# power_POS3V3.net
KiCad netlist of a schematic drawn in Altium Designer
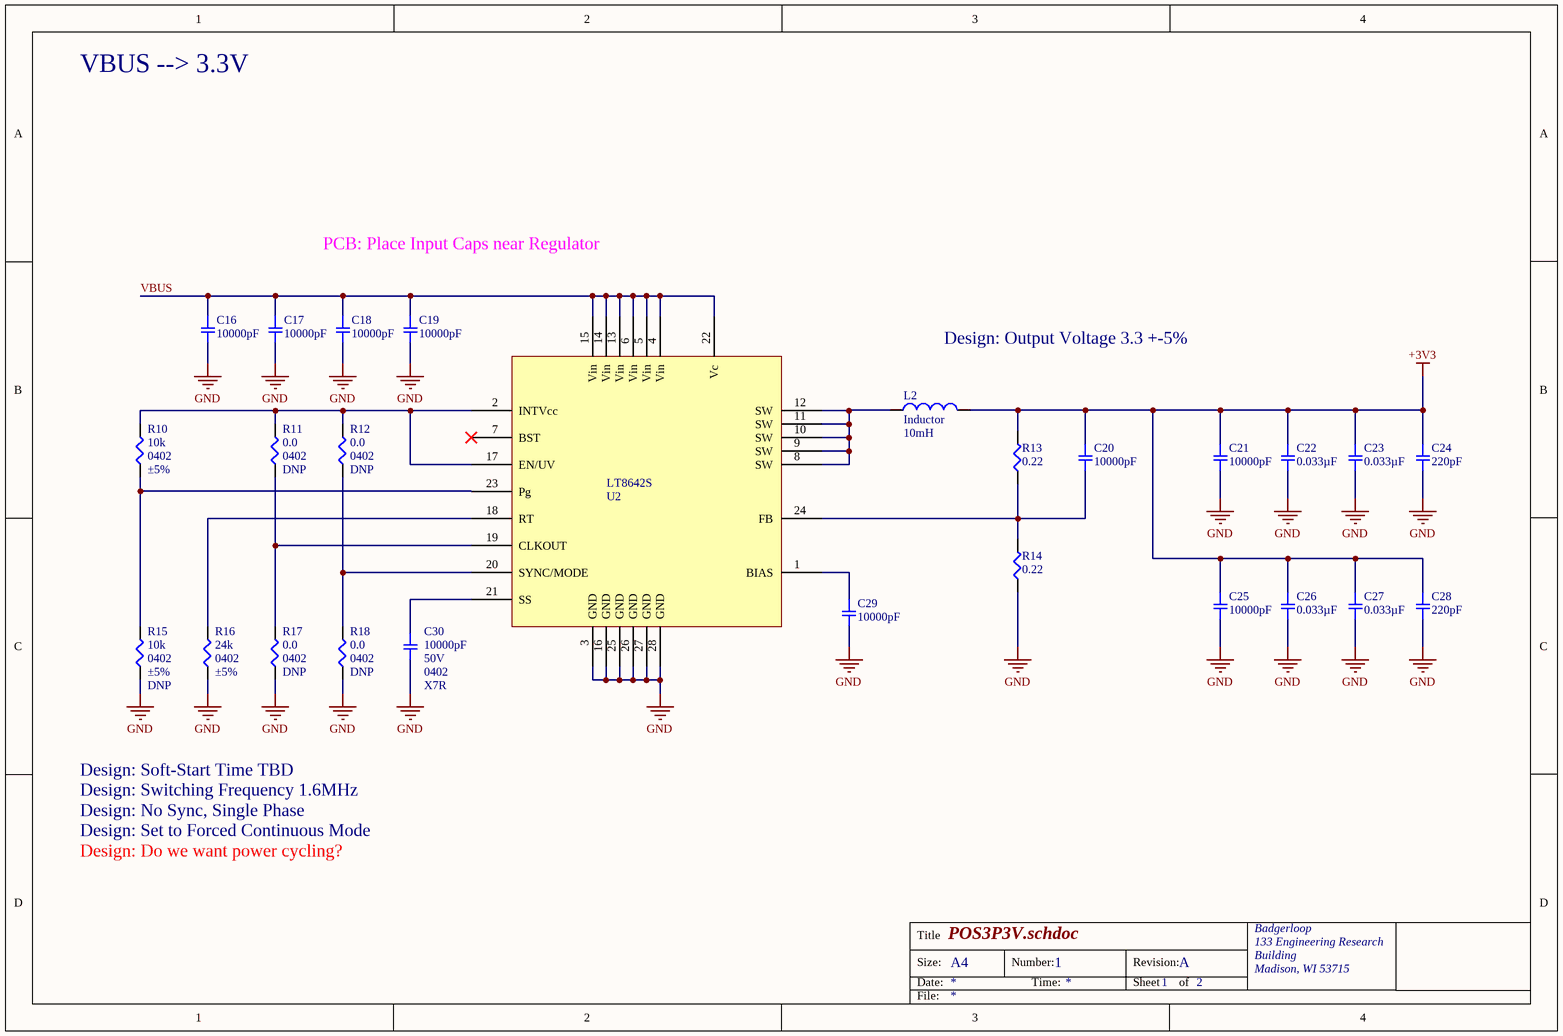
[diagram p0: power_POS3V3.schdoc]

(export (version "E")
  (design (tool "Eeschema 10.0.6"))
  (components
    (comp (ref "C16")
      (value "10000pF")
      (footprint "SMD-0805C")
      (description "CAP CER 10000PF 250V X7T 0805")
      (fields
        (field (name "DIGI-KEY PART NUMBER") "490-13986-1-ND")
        (field (name "PART NUMBER") "GC321AD72E103KX01D")
      )
      (libsource (lib "capacitor") (part "GC321AD72E103KX01D"))
    )
    (comp (ref "C17")
      (value "10000pF")
      (footprint "SMD-0805C")
      (description "CAP CER 10000PF 250V X7T 0805")
      (fields
        (field (name "DIGI-KEY PART NUMBER") "490-13986-1-ND")
        (field (name "PART NUMBER") "GC321AD72E103KX01D")
      )
      (libsource (lib "capacitor") (part "GC321AD72E103KX01D"))
    )
    (comp (ref "C18")
      (value "10000pF")
      (footprint "SMD-0805C")
      (description "CAP CER 10000PF 250V X7T 0805")
      (fields
        (field (name "DIGI-KEY PART NUMBER") "490-13986-1-ND")
        (field (name "PART NUMBER") "GC321AD72E103KX01D")
      )
      (libsource (lib "capacitor") (part "GC321AD72E103KX01D"))
    )
    (comp (ref "C19")
      (value "10000pF")
      (footprint "SMD-0805C")
      (description "CAP CER 10000PF 250V X7T 0805")
      (fields
        (field (name "DIGI-KEY PART NUMBER") "490-13986-1-ND")
        (field (name "PART NUMBER") "GC321AD72E103KX01D")
      )
      (libsource (lib "capacitor") (part "GC321AD72E103KX01D"))
    )
    (comp (ref "C20")
      (value "10000pF")
      (footprint "SMD-0805C")
      (description "CAP CER 10000PF 250V X7T 0805")
      (fields
        (field (name "DIGI-KEY PART NUMBER") "490-13986-1-ND")
        (field (name "PART NUMBER") "GC321AD72E103KX01D")
      )
      (libsource (lib "capacitor") (part "GC321AD72E103KX01D"))
    )
    (comp (ref "C21")
      (value "10000pF")
      (footprint "SMD-0805C")
      (description "CAP CER 10000PF 250V X7T 0805")
      (fields
        (field (name "DIGI-KEY PART NUMBER") "490-13986-1-ND")
        (field (name "PART NUMBER") "GC321AD72E103KX01D")
      )
      (libsource (lib "capacitor") (part "GC321AD72E103KX01D"))
    )
    (comp (ref "C22")
      (value "0.033µF")
      (footprint "SMD-1206C")
      (description "CAP CER 0.033UF 250V X7T 1206")
      (fields
        (field (name "DIGI-KEY PART NUMBER") "490-13989-1-ND")
        (field (name "PART NUMBER") "GC331AD72E333KX01D")
      )
      (libsource (lib "capacitor") (part "GC331AD72E333KX01D"))
    )
    (comp (ref "C23")
      (value "0.033µF")
      (footprint "SMD-1206C")
      (description "CAP CER 0.033UF 250V X7T 1206")
      (fields
        (field (name "DIGI-KEY PART NUMBER") "490-13989-1-ND")
        (field (name "PART NUMBER") "GC331AD72E333KX01D")
      )
      (libsource (lib "capacitor") (part "GC331AD72E333KX01D"))
    )
    (comp (ref "C24")
      (value "220pF")
      (footprint "SMD-0402C")
      (description "CAP CER 220PF 50V NP0 0402")
      (fields
        (field (name "DIGI-KEY PART NUMBER") "490-4927-1-ND")
        (field (name "PART NUMBER") "GCM1555C1H221JA16D")
      )
      (libsource (lib "capacitor") (part "GCM1555C1H221JA16D"))
    )
    (comp (ref "C25")
      (value "10000pF")
      (footprint "SMD-0805C")
      (description "CAP CER 10000PF 250V X7T 0805")
      (fields
        (field (name "DIGI-KEY PART NUMBER") "490-13986-1-ND")
        (field (name "PART NUMBER") "GC321AD72E103KX01D")
      )
      (libsource (lib "capacitor") (part "GC321AD72E103KX01D"))
    )
    (comp (ref "C26")
      (value "0.033µF")
      (footprint "SMD-1206C")
      (description "CAP CER 0.033UF 250V X7T 1206")
      (fields
        (field (name "DIGI-KEY PART NUMBER") "490-13989-1-ND")
        (field (name "PART NUMBER") "GC331AD72E333KX01D")
      )
      (libsource (lib "capacitor") (part "GC331AD72E333KX01D"))
    )
    (comp (ref "C27")
      (value "0.033µF")
      (footprint "SMD-1206C")
      (description "CAP CER 0.033UF 250V X7T 1206")
      (fields
        (field (name "DIGI-KEY PART NUMBER") "490-13989-1-ND")
        (field (name "PART NUMBER") "GC331AD72E333KX01D")
      )
      (libsource (lib "capacitor") (part "GC331AD72E333KX01D"))
    )
    (comp (ref "C28")
      (value "220pF")
      (footprint "SMD-0402C")
      (description "CAP CER 220PF 50V NP0 0402")
      (fields
        (field (name "DIGI-KEY PART NUMBER") "490-4927-1-ND")
        (field (name "PART NUMBER") "GCM1555C1H221JA16D")
      )
      (libsource (lib "capacitor") (part "GCM1555C1H221JA16D"))
    )
    (comp (ref "C29")
      (value "10000pF")
      (footprint "SMD-0805C")
      (description "CAP CER 10000PF 250V X7T 0805")
      (fields
        (field (name "DIGI-KEY PART NUMBER") "490-13986-1-ND")
        (field (name "PART NUMBER") "GC321AD72E103KX01D")
      )
      (libsource (lib "capacitor") (part "GC321AD72E103KX01D"))
    )
    (comp (ref "C30")
      (value "10000pF")
      (footprint "SMD-0402C")
      (description "CAP CER 10000PF 50V X7R 0402")
      (fields
        (field (name "DIGI-KEY PART NUMBER") "490-4762-1-ND")
        (field (name "PART NUMBER") "GCM155R71H103KA55D")
        (field (name "VOLTAGE") "50V")
        (field (name "TEMPERATURE COEFFICIENT") "X7R")
        (field (name "PACKAGE / CASE") "0402")
      )
      (libsource (lib "capacitor") (part "GCM155R71H103KA55D"))
    )
    (comp (ref "L2")
      (value "Inductor")
      (footprint "0402-A")
      (fields (field (name "ALTIUM_VALUE") "10mH") (field (name "PUBLISHER") "Altium Limited"))
      (libsource (lib "Miscellaneous Devices") (part "Inductor"))
    )
    (comp (ref "R10")
      (value "10k")
      (footprint "SMD-0402-RES")
      (description "RES SMD 10K OHM 5% 1/10W 0402")
      (fields
        (field (name "PART NUMBER") "ERJ-2GEJ103X")
        (field (name "DIGI-KEY PART NUMBER") "P10KJCT-ND")
        (field (name "TOLERANCE") "±5%")
        (field (name "SUPPLIER DEVICE PACKAGE") "0402")
      )
      (libsource (lib "resistor") (part "ERJ-2GEJ103X"))
    )
    (comp (ref "R11")
      (value "0.0")
      (footprint "SMD-0402-RES")
      (description "RES SMD 0.0OHM JUMPER 1/10W 0402")
      (fields
        (field (name "PART NUMBER") "ERJ-2GE0R00X")
        (field (name "DIGI-KEY PART NUMBER") "P0.0JCT-ND")
        (field (name "SUPPLIER DEVICE PACKAGE") "0402")
        (field (name "BOM") "DNP")
      )
      (libsource (lib "resistor") (part "ERJ-2GE0R00X"))
    )
    (comp (ref "R12")
      (value "0.0")
      (footprint "SMD-0402-RES")
      (description "RES SMD 0.0OHM JUMPER 1/10W 0402")
      (fields
        (field (name "PART NUMBER") "ERJ-2GE0R00X")
        (field (name "DIGI-KEY PART NUMBER") "P0.0JCT-ND")
        (field (name "SUPPLIER DEVICE PACKAGE") "0402")
        (field (name "BOM") "DNP")
      )
      (libsource (lib "resistor") (part "ERJ-2GE0R00X"))
    )
    (comp (ref "R13")
      (value "0.22")
      (footprint "SMD-0402-RES")
      (description "RES SMD 0.22 OHM 1% 1/6W 0402")
      (fields (field (name "PART NUMBER") "ERJ-2BQFR22X") (field (name "DIGI-KEY PART NUMBER") "P.22AKCT-ND"))
      (libsource (lib "resistor") (part "ERJ-2BQFR22X"))
    )
    (comp (ref "R14")
      (value "0.22")
      (footprint "SMD-0402-RES")
      (description "RES SMD 0.22 OHM 1% 1/6W 0402")
      (fields (field (name "PART NUMBER") "ERJ-2BQFR22X") (field (name "DIGI-KEY PART NUMBER") "P.22AKCT-ND"))
      (libsource (lib "resistor") (part "ERJ-2BQFR22X"))
    )
    (comp (ref "R15")
      (value "10k")
      (footprint "SMD-0402-RES")
      (description "RES SMD 10K OHM 5% 1/10W 0402")
      (fields
        (field (name "PART NUMBER") "ERJ-2GEJ103X")
        (field (name "DIGI-KEY PART NUMBER") "P10KJCT-ND")
        (field (name "TOLERANCE") "±5%")
        (field (name "SUPPLIER DEVICE PACKAGE") "0402")
        (field (name "BOM_CONFIG") "DNP")
      )
      (libsource (lib "resistor") (part "ERJ-2GEJ103X"))
    )
    (comp (ref "R16")
      (value "24k")
      (footprint "SMD-0402-RES")
      (description "RES SMD 24K OHM 5% 1/10W 0402")
      (fields
        (field (name "PART NUMBER") "ERJ-2GEJ243X")
        (field (name "DIGI-KEY PART NUMBER") "P24KJCT-ND")
        (field (name "TOLERANCE") "±5%")
        (field (name "SUPPLIER DEVICE PACKAGE") "0402")
      )
      (libsource (lib "resistor") (part "ERJ-2GEJ243X"))
    )
    (comp (ref "R17")
      (value "0.0")
      (footprint "SMD-0402-RES")
      (description "RES SMD 0.0OHM JUMPER 1/10W 0402")
      (fields
        (field (name "PART NUMBER") "ERJ-2GE0R00X")
        (field (name "DIGI-KEY PART NUMBER") "P0.0JCT-ND")
        (field (name "SUPPLIER DEVICE PACKAGE") "0402")
        (field (name "BOM") "DNP")
      )
      (libsource (lib "resistor") (part "ERJ-2GE0R00X"))
    )
    (comp (ref "R18")
      (value "0.0")
      (footprint "SMD-0402-RES")
      (description "RES SMD 0.0OHM JUMPER 1/10W 0402")
      (fields
        (field (name "PART NUMBER") "ERJ-2GE0R00X")
        (field (name "DIGI-KEY PART NUMBER") "P0.0JCT-ND")
        (field (name "SUPPLIER DEVICE PACKAGE") "0402")
        (field (name "BOM") "DNP")
      )
      (libsource (lib "resistor") (part "ERJ-2GE0R00X"))
    )
    (comp (ref "U2")
      (value "LT8642S")
      (description "18V, 10A Synchronous\r\nStep-Down Silent Switcher 2")
      (libsource (lib "ic") (part "LT8642S"))
    )
  )
  (nets
    (net (code "1") (name "+3V3") (class "Default")
      (node (ref "C20") (pin "1") (pinfunction "1_1") (pintype "passive"))
      (node (ref "C21") (pin "1") (pinfunction "1_1") (pintype "passive"))
      (node (ref "C22") (pin "1") (pinfunction "1_1") (pintype "passive"))
      (node (ref "C23") (pin "1") (pinfunction "1_1") (pintype "passive"))
      (node (ref "C24") (pin "1") (pinfunction "1_1") (pintype "passive"))
      (node (ref "C25") (pin "1") (pinfunction "1_1") (pintype "passive"))
      (node (ref "C26") (pin "1") (pinfunction "1_1") (pintype "passive"))
      (node (ref "C27") (pin "1") (pinfunction "1_1") (pintype "passive"))
      (node (ref "C28") (pin "1") (pinfunction "1_1") (pintype "passive"))
      (node (ref "L2") (pin "2") (pinfunction "2_2") (pintype "passive"))
      (node (ref "R13") (pin "2") (pinfunction "2_2") (pintype "passive"))
    )
    (net (code "2") (name "/VBUS") (class "Default")
      (node (ref "C16") (pin "1") (pinfunction "1_1") (pintype "passive"))
      (node (ref "C17") (pin "1") (pinfunction "1_1") (pintype "passive"))
      (node (ref "C18") (pin "1") (pinfunction "1_1") (pintype "passive"))
      (node (ref "C19") (pin "1") (pinfunction "1_1") (pintype "passive"))
      (node (ref "U2") (pin "13") (pinfunction "Vin_13") (pintype "power_in"))
      (node (ref "U2") (pin "14") (pinfunction "Vin_14") (pintype "power_in"))
      (node (ref "U2") (pin "15") (pinfunction "Vin_15") (pintype "power_in"))
      (node (ref "U2") (pin "22") (pinfunction "Vc_22") (pintype "passive"))
      (node (ref "U2") (pin "4") (pinfunction "Vin_4") (pintype "power_in"))
      (node (ref "U2") (pin "5") (pinfunction "Vin_5") (pintype "power_in"))
      (node (ref "U2") (pin "6") (pinfunction "Vin_6") (pintype "power_in"))
    )
    (net (code "3") (name "GND") (class "Default")
      (node (ref "C16") (pin "2") (pinfunction "2_2") (pintype "passive"))
      (node (ref "C17") (pin "2") (pinfunction "2_2") (pintype "passive"))
      (node (ref "C18") (pin "2") (pinfunction "2_2") (pintype "passive"))
      (node (ref "C19") (pin "2") (pinfunction "2_2") (pintype "passive"))
      (node (ref "C21") (pin "2") (pinfunction "2_2") (pintype "passive"))
      (node (ref "C22") (pin "2") (pinfunction "2_2") (pintype "passive"))
      (node (ref "C23") (pin "2") (pinfunction "2_2") (pintype "passive"))
      (node (ref "C24") (pin "2") (pinfunction "2_2") (pintype "passive"))
      (node (ref "C25") (pin "2") (pinfunction "2_2") (pintype "passive"))
      (node (ref "C26") (pin "2") (pinfunction "2_2") (pintype "passive"))
      (node (ref "C27") (pin "2") (pinfunction "2_2") (pintype "passive"))
      (node (ref "C28") (pin "2") (pinfunction "2_2") (pintype "passive"))
      (node (ref "C29") (pin "2") (pinfunction "2_2") (pintype "passive"))
      (node (ref "C30") (pin "2") (pinfunction "2_2") (pintype "passive"))
      (node (ref "R14") (pin "1") (pinfunction "1_1") (pintype "passive"))
      (node (ref "R15") (pin "1") (pinfunction "1_1") (pintype "passive"))
      (node (ref "R16") (pin "1") (pinfunction "1_1") (pintype "passive"))
      (node (ref "R17") (pin "1") (pinfunction "1_1") (pintype "passive"))
      (node (ref "R18") (pin "1") (pinfunction "1_1") (pintype "passive"))
      (node (ref "U2") (pin "16") (pinfunction "GND_16") (pintype "power_in"))
      (node (ref "U2") (pin "25") (pinfunction "GND_25") (pintype "power_in"))
      (node (ref "U2") (pin "26") (pinfunction "GND_26") (pintype "power_in"))
      (node (ref "U2") (pin "27") (pinfunction "GND_27") (pintype "power_in"))
      (node (ref "U2") (pin "28") (pinfunction "GND_28") (pintype "power_in"))
      (node (ref "U2") (pin "3") (pinfunction "GND_3") (pintype "power_in"))
    )
    (net (code "4") (name "Net-(L2-Pad1)") (class "Default")
      (node (ref "L2") (pin "1") (pinfunction "1_1") (pintype "passive"))
      (node (ref "U2") (pin "10") (pinfunction "SW_10") (pintype "passive"))
      (node (ref "U2") (pin "11") (pinfunction "SW_11") (pintype "passive"))
      (node (ref "U2") (pin "12") (pinfunction "SW_12") (pintype "passive"))
      (node (ref "U2") (pin "8") (pinfunction "SW_8") (pintype "passive"))
      (node (ref "U2") (pin "9") (pinfunction "SW_9") (pintype "passive"))
    )
    (net (code "5") (name "Net-(U2-BIAS)") (class "Default")
      (node (ref "C29") (pin "1") (pinfunction "1_1") (pintype "passive"))
      (node (ref "U2") (pin "1") (pinfunction "BIAS_1") (pintype "passive"))
    )
    (net (code "6") (name "Net-(U2-CLKOUT)") (class "Default")
      (node (ref "R11") (pin "1") (pinfunction "1_1") (pintype "passive"))
      (node (ref "R17") (pin "2") (pinfunction "2_2") (pintype "passive"))
      (node (ref "U2") (pin "19") (pinfunction "CLKOUT_19") (pintype "passive"))
    )
    (net (code "7") (name "Net-(U2-EN{slash}UV)") (class "Default")
      (node (ref "R10") (pin "2") (pinfunction "2_2") (pintype "passive"))
      (node (ref "R11") (pin "2") (pinfunction "2_2") (pintype "passive"))
      (node (ref "R12") (pin "2") (pinfunction "2_2") (pintype "passive"))
      (node (ref "U2") (pin "17") (pinfunction "EN/UV_17") (pintype "passive"))
      (node (ref "U2") (pin "2") (pinfunction "INTVcc_2") (pintype "passive"))
    )
    (net (code "8") (name "Net-(U2-FB)") (class "Default")
      (node (ref "C20") (pin "2") (pinfunction "2_2") (pintype "passive"))
      (node (ref "R13") (pin "1") (pinfunction "1_1") (pintype "passive"))
      (node (ref "R14") (pin "2") (pinfunction "2_2") (pintype "passive"))
      (node (ref "U2") (pin "24") (pinfunction "FB_24") (pintype "passive"))
    )
    (net (code "9") (name "Net-(U2-Pg)") (class "Default")
      (node (ref "R10") (pin "1") (pinfunction "1_1") (pintype "passive"))
      (node (ref "R15") (pin "2") (pinfunction "2_2") (pintype "passive"))
      (node (ref "U2") (pin "23") (pinfunction "Pg_23") (pintype "passive"))
    )
    (net (code "10") (name "Net-(U2-RT)") (class "Default")
      (node (ref "R16") (pin "2") (pinfunction "2_2") (pintype "passive"))
      (node (ref "U2") (pin "18") (pinfunction "RT_18") (pintype "passive"))
    )
    (net (code "11") (name "Net-(U2-SS)") (class "Default")
      (node (ref "C30") (pin "1") (pinfunction "1_1") (pintype "passive"))
      (node (ref "U2") (pin "21") (pinfunction "SS_21") (pintype "passive"))
    )
    (net (code "12") (name "Net-(U2-SYNC{slash}MODE)") (class "Default")
      (node (ref "R12") (pin "1") (pinfunction "1_1") (pintype "passive"))
      (node (ref "R18") (pin "2") (pinfunction "2_2") (pintype "passive"))
      (node (ref "U2") (pin "20") (pinfunction "SYNC/MODE_20") (pintype "passive"))
    )
    (net (code "13") (name "unconnected-(U2-BST-Pad7)") (class "Default")
      (node (ref "U2") (pin "7") (pinfunction "BST_7") (pintype "passive+no_connect"))
    )
  )
)
